# Dimmer.net
KiCad netlist of a schematic drawn in Altium Designer
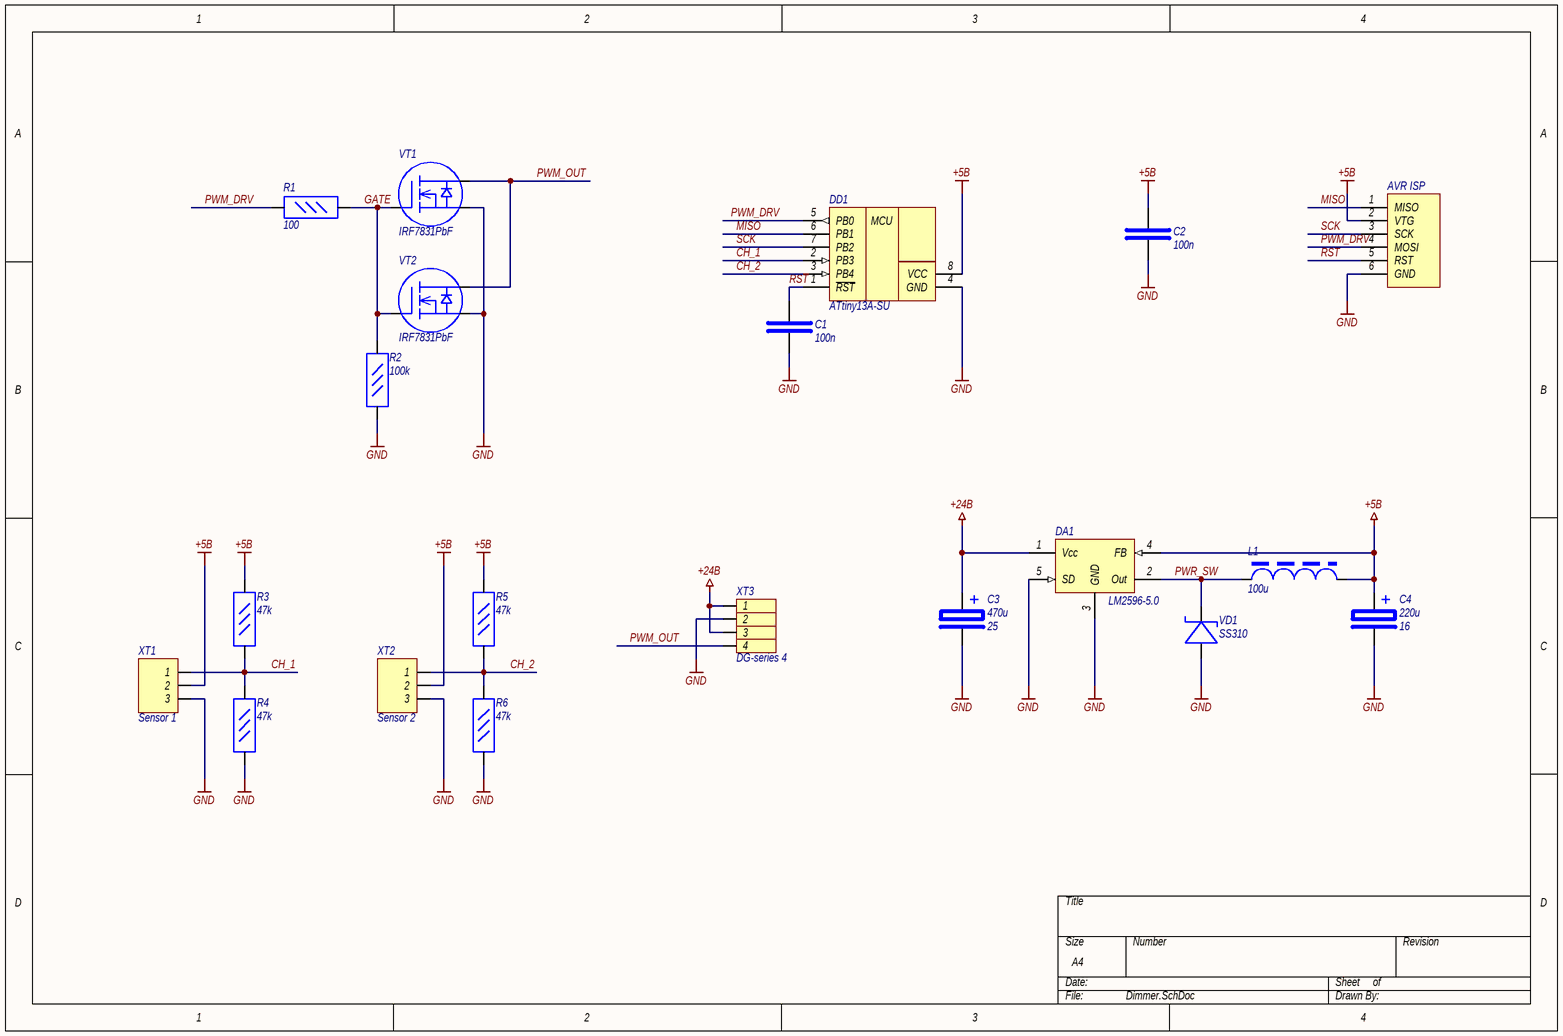
[diagram p0: Dimmer.SchDoc]

(export (version "E")
  (design (tool "Eeschema 10.0.6"))
  (components
    (comp (ref "C1")
      (value "100n")
      (footprint "CC0603")
      (description "Ceramic Capacitor")
      (libsource (lib "Passive") (part "Ceramic Capacitor"))
    )
    (comp (ref "C2")
      (value "100n")
      (footprint "CC0603")
      (description "Ceramic Capacitor")
      (libsource (lib "Passive") (part "Ceramic Capacitor"))
    )
    (comp (ref "C3")
      (value "470u")
      (footprint "CE 8x16-3.5")
      (description "Polarized electrolythic capacitor")
      (fields (field (name "UMAX") "25"))
      (libsource (lib "Passive") (part "Electrolythic Capacitor"))
    )
    (comp (ref "C4")
      (value "220u")
      (footprint "CE 6.3x12-2.5")
      (description "Polarized electrolythic capacitor")
      (fields (field (name "UMAX") "16"))
      (libsource (lib "Passive") (part "Electrolythic Capacitor"))
    )
    (comp (ref "DA1")
      (value "LM2596-5.0")
      (footprint "TO-263-5")
      (description "4.5V to 40V, 3A Low Component Count Step-Down Regulator")
      (libsource (lib "Analog chips") (part "LM2596-5.0"))
    )
    (comp (ref "DD1")
      (value "ATtiny13A-SU")
      (footprint "SOIC-8-208")
      (description "8-bit AVR microcontroller")
      (libsource (lib "Atmel") (part "ATtiny13A"))
    )
    (comp (ref "ISP") (value "AVR ISP") (footprint "ISP-6") (libsource (lib "Connectors") (part "AVR ISP")))
    (comp (ref "L1")
      (value "100u")
      (footprint "HA78D")
      (description "Abstract inductor with non-conductive core")
      (libsource (lib "Passive") (part "Inductor non-conductive core"))
    )
    (comp (ref "R1")
      (value "100")
      (footprint "RL0603")
      (description "Chip Resistor 1/16W")
      (libsource (lib "Passive") (part "Resistor 1/16W"))
    )
    (comp (ref "R2")
      (value "100k")
      (footprint "RL0603")
      (description "Chip Resistor 1/16W")
      (libsource (lib "Passive") (part "Resistor 1/16W"))
    )
    (comp (ref "R3")
      (value "47k")
      (footprint "RL0603")
      (description "Chip Resistor 1/16W")
      (libsource (lib "Passive") (part "Resistor 1/16W"))
    )
    (comp (ref "R4")
      (value "47k")
      (footprint "RL0603")
      (description "Chip Resistor 1/16W")
      (libsource (lib "Passive") (part "Resistor 1/16W"))
    )
    (comp (ref "R5")
      (value "47k")
      (footprint "RL0603")
      (description "Chip Resistor 1/16W")
      (libsource (lib "Passive") (part "Resistor 1/16W"))
    )
    (comp (ref "R6")
      (value "47k")
      (footprint "RL0603")
      (description "Chip Resistor 1/16W")
      (libsource (lib "Passive") (part "Resistor 1/16W"))
    )
    (comp (ref "VD1")
      (value "SS310")
      (footprint "DO-214AA")
      (description "Rectifier Schottky diode")
      (libsource (lib "Diodes") (part "SS310"))
    )
    (comp (ref "VT1")
      (value "IRF7831PbF")
      (footprint "SOIC-8-150-SSSGDDDD")
      (description "N-channel Power MOSFET")
      (libsource (lib "Transistors") (part "IRF7831PbF"))
    )
    (comp (ref "VT2")
      (value "IRF7831PbF")
      (footprint "SOIC-8-150-SSSGDDDD")
      (description "N-channel Power MOSFET")
      (libsource (lib "Transistors") (part "IRF7831PbF"))
    )
    (comp (ref "XT1")
      (value "Sensor 1")
      (footprint "HDR1X3")
      (description "Header, 3-Pin")
      (libsource (lib "Connectors") (part "Header 3"))
    )
    (comp (ref "XT2")
      (value "Sensor 2")
      (footprint "HDR1X3")
      (description "Header, 3-Pin")
      (libsource (lib "Connectors") (part "Header 3"))
    )
    (comp (ref "XT3")
      (value "DG-series 4")
      (footprint "DG126-5.0-04P")
      (description "Terminal block")
      (libsource (lib "Connectors") (part "DG-series 4"))
    )
  )
  (nets
    (net (code "1") (name "+5В") (class "Default")
      (node (ref "C2") (pin "2") (pinfunction "2_2") (pintype "passive"))
      (node (ref "C4") (pin "2") (pinfunction "2_2") (pintype "passive"))
      (node (ref "DA1") (pin "4") (pinfunction "FB_4") (pintype "input"))
      (node (ref "DD1") (pin "8") (pinfunction "VCC_8") (pintype "power_in"))
      (node (ref "ISP") (pin "2") (pinfunction "VTG_2") (pintype "passive"))
      (node (ref "L1") (pin "2") (pinfunction "2_2") (pintype "passive"))
      (node (ref "R3") (pin "2") (pinfunction "2_2") (pintype "passive"))
      (node (ref "R5") (pin "2") (pinfunction "2_2") (pintype "passive"))
      (node (ref "XT1") (pin "2") (pinfunction "2_2") (pintype "passive"))
      (node (ref "XT2") (pin "2") (pinfunction "2_2") (pintype "passive"))
    )
    (net (code "2") (name "+24В") (class "Default")
      (node (ref "C3") (pin "2") (pinfunction "2_2") (pintype "passive"))
      (node (ref "DA1") (pin "1") (pinfunction "Vcc_1") (pintype "power_in"))
      (node (ref "XT3") (pin "1") (pinfunction "1_1") (pintype "passive"))
      (node (ref "XT3") (pin "3") (pinfunction "3_3") (pintype "passive"))
    )
    (net (code "3") (name "/CH_1") (class "Default")
      (node (ref "DD1") (pin "2") (pinfunction "PB3_2") (pintype "input"))
      (node (ref "R3") (pin "1") (pinfunction "1_1") (pintype "passive"))
      (node (ref "R4") (pin "2") (pinfunction "2_2") (pintype "passive"))
      (node (ref "XT1") (pin "1") (pinfunction "1_1") (pintype "passive"))
    )
    (net (code "4") (name "/CH_2") (class "Default")
      (node (ref "DD1") (pin "3") (pinfunction "PB4_3") (pintype "input"))
      (node (ref "R5") (pin "1") (pinfunction "1_1") (pintype "passive"))
      (node (ref "R6") (pin "2") (pinfunction "2_2") (pintype "passive"))
      (node (ref "XT2") (pin "1") (pinfunction "1_1") (pintype "passive"))
    )
    (net (code "5") (name "/GATE") (class "Default")
      (node (ref "R1") (pin "2") (pinfunction "2_2") (pintype "passive"))
      (node (ref "R2") (pin "2") (pinfunction "2_2") (pintype "passive"))
      (node (ref "VT1") (pin "G") (pinfunction "G_G") (pintype "passive"))
      (node (ref "VT2") (pin "G") (pinfunction "G_G") (pintype "passive"))
    )
    (net (code "6") (name "/MISO") (class "Default")
      (node (ref "DD1") (pin "6") (pinfunction "PB1_6") (pintype "passive"))
      (node (ref "ISP") (pin "1") (pinfunction "MISO_1") (pintype "passive"))
    )
    (net (code "7") (name "/PWM_DRV") (class "Default")
      (node (ref "DD1") (pin "5") (pinfunction "PB0_5") (pintype "output"))
      (node (ref "ISP") (pin "4") (pinfunction "MOSI_4") (pintype "passive"))
      (node (ref "R1") (pin "1") (pinfunction "1_1") (pintype "passive"))
    )
    (net (code "8") (name "/PWM_OUT") (class "Default")
      (node (ref "VT1") (pin "D") (pinfunction "D_D") (pintype "passive"))
      (node (ref "VT2") (pin "D") (pinfunction "D_D") (pintype "passive"))
      (node (ref "XT3") (pin "4") (pinfunction "4_4") (pintype "passive"))
    )
    (net (code "9") (name "/PWR_SW") (class "Default")
      (node (ref "DA1") (pin "2") (pinfunction "Out_2") (pintype "power_in"))
      (node (ref "L1") (pin "1") (pinfunction "1_1") (pintype "passive"))
      (node (ref "VD1") (pin "C") (pinfunction "Cathode_C") (pintype "passive"))
    )
    (net (code "10") (name "/RST") (class "Default")
      (node (ref "C1") (pin "2") (pinfunction "2_2") (pintype "passive"))
      (node (ref "DD1") (pin "1") (pinfunction "RST_1") (pintype "passive"))
      (node (ref "ISP") (pin "5") (pinfunction "RST_5") (pintype "passive"))
    )
    (net (code "11") (name "/SCK") (class "Default")
      (node (ref "DD1") (pin "7") (pinfunction "PB2_7") (pintype "passive"))
      (node (ref "ISP") (pin "3") (pinfunction "SCK_3") (pintype "passive"))
    )
    (net (code "12") (name "GND") (class "Default")
      (node (ref "C1") (pin "1") (pinfunction "1_1") (pintype "passive"))
      (node (ref "C2") (pin "1") (pinfunction "1_1") (pintype "passive"))
      (node (ref "C3") (pin "1") (pinfunction "1_1") (pintype "passive"))
      (node (ref "C4") (pin "1") (pinfunction "1_1") (pintype "passive"))
      (node (ref "DA1") (pin "3") (pinfunction "GND_3") (pintype "power_in"))
      (node (ref "DA1") (pin "5") (pinfunction "SD_5") (pintype "input"))
      (node (ref "DD1") (pin "4") (pinfunction "GND_4") (pintype "power_in"))
      (node (ref "ISP") (pin "6") (pinfunction "GND_6") (pintype "passive"))
      (node (ref "R2") (pin "1") (pinfunction "1_1") (pintype "passive"))
      (node (ref "R4") (pin "1") (pinfunction "1_1") (pintype "passive"))
      (node (ref "R6") (pin "1") (pinfunction "1_1") (pintype "passive"))
      (node (ref "VD1") (pin "A") (pinfunction "Anode_A") (pintype "passive"))
      (node (ref "VT1") (pin "S") (pinfunction "S_S") (pintype "passive"))
      (node (ref "VT2") (pin "S") (pinfunction "S_S") (pintype "passive"))
      (node (ref "XT1") (pin "3") (pinfunction "3_3") (pintype "passive"))
      (node (ref "XT2") (pin "3") (pinfunction "3_3") (pintype "passive"))
      (node (ref "XT3") (pin "2") (pinfunction "2_2") (pintype "passive"))
    )
  )
)
